# Assign.net
KiCad netlist of a schematic drawn in Altium Designer
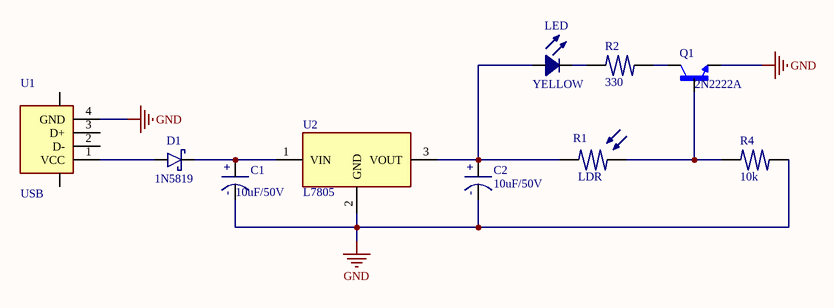
[diagram p0: Assign.SchDoc]

(export (version "E")
  (design (tool "Eeschema 10.0.6"))
  (components
    (comp (ref "C1")
      (value "10uF/50V")
      (footprint "10uF/50V")
      (description "Electrolytic Capacitor 10uF/50V")
      (libsource (lib "Electrolytic Capacitor") (part "10uF/50V"))
    )
    (comp (ref "C2")
      (value "10uF/50V")
      (footprint "10uF/50V")
      (description "Electrolytic Capacitor 10uF/50V")
      (libsource (lib "Electrolytic Capacitor") (part "10uF/50V"))
    )
    (comp (ref "D1")
      (value "1N5819")
      (footprint "1N5819")
      (description "Rectifier Schottky 40V 1A DO-15")
      (libsource (lib "Diode") (part "1N5819"))
    )
    (comp (ref "LED")
      (value "YELLOW")
      (footprint "LED_0805_YELLOW")
      (description "LED 0805 Yellow.")
      (libsource (lib "LED") (part "LED_0805_YELLOW"))
    )
    (comp (ref "Q1")
      (value "2N2222A")
      (footprint "TO92254P470H750-3")
      (description "Bipolar (BJT) Transistor NPN 40 V 600 mA 250MHz 625 mW Through Hole TO-92")
      (fields (field (name "MF") "Diotec Semiconductor"))
      (libsource (lib "2N2222A") (part "2N2222A"))
    )
    (comp (ref "R1")
      (value "LDR")
      (footprint "LDR")
      (description "LIGHT DEPENDEND RESISTOR/PHOTORESITOR")
      (libsource (lib "Sensors") (part "LDR"))
    )
    (comp (ref "R2")
      (value "330")
      (footprint "RESISTOR_PTH_9.5mm")
      (description "Generic Resistor 9.5mm.")
      (libsource (lib "Resistors") (part "RESISTOR_9.5mm"))
    )
    (comp (ref "R4")
      (value "10k")
      (footprint "RESISTOR_PTH_9.5mm")
      (description "Generic Resistor 9.5mm.")
      (libsource (lib "Resistors") (part "RESISTOR_9.5mm"))
    )
    (comp (ref "U1") (value "USB") (footprint "USB") (libsource (lib "Connectors") (part "USB")))
    (comp (ref "U2")
      (value "L7805")
      (footprint "L7805_smd")
      (description "IC REG LINEAR 5V 1.5A TO220AB")
      (libsource (lib "Voltage Regulators") (part "L7805"))
    )
  )
  (nets
    (net (code "1") (name "GND") (class "Default")
      (node (ref "C1") (pin "1") (pinfunction "1_1") (pintype "passive"))
      (node (ref "C2") (pin "1") (pinfunction "1_1") (pintype "passive"))
      (node (ref "Q1") (pin "1") (pinfunction "E_1") (pintype "passive"))
      (node (ref "R4") (pin "2") (pinfunction "2_2") (pintype "passive"))
      (node (ref "U1") (pin "4") (pinfunction "GND_4") (pintype "passive"))
      (node (ref "U2") (pin "2") (pinfunction "GND_2") (pintype "passive"))
    )
    (net (code "2") (name "Net-(C1-_2)") (class "Default")
      (node (ref "C1") (pin "2") (pinfunction "_2_2") (pintype "passive"))
      (node (ref "D1") (pin "2") (pintype "passive"))
      (node (ref "U2") (pin "1") (pinfunction "VIN_1") (pintype "passive"))
    )
    (net (code "3") (name "Net-(C2-_2)") (class "Default")
      (node (ref "C2") (pin "2") (pinfunction "_2_2") (pintype "passive"))
      (node (ref "LED") (pin "1") (pinfunction "1_1") (pintype "passive"))
      (node (ref "R1") (pin "1") (pinfunction "1_1") (pintype "passive"))
      (node (ref "U2") (pin "3") (pinfunction "VOUT_3") (pintype "passive"))
    )
    (net (code "4") (name "Net-(LED-Pad2)") (class "Default")
      (node (ref "LED") (pin "2") (pinfunction "2_2") (pintype "passive"))
      (node (ref "R2") (pin "1") (pinfunction "1_1") (pintype "passive"))
    )
    (net (code "5") (name "Net-(Q1-B)") (class "Default")
      (node (ref "Q1") (pin "2") (pinfunction "B_2") (pintype "passive"))
      (node (ref "R1") (pin "2") (pinfunction "2_2") (pintype "passive"))
      (node (ref "R4") (pin "1") (pinfunction "1_1") (pintype "passive"))
    )
    (net (code "6") (name "Net-(Q1-C)") (class "Default")
      (node (ref "Q1") (pin "3") (pinfunction "C_3") (pintype "passive"))
      (node (ref "R2") (pin "2") (pinfunction "2_2") (pintype "passive"))
    )
    (net (code "7") (name "Net-(U1-VCC)") (class "Default")
      (node (ref "D1") (pin "1") (pinfunction "1_1") (pintype "passive"))
      (node (ref "U1") (pin "1") (pinfunction "VCC_1") (pintype "passive"))
    )
    (net (code "8") (name "unconnected-(U1-D+-Pad3)") (class "Default")
      (node (ref "U1") (pin "3") (pinfunction "D+_3") (pintype "passive"))
    )
    (net (code "9") (name "unconnected-(U1-D--Pad2)") (class "Default")
      (node (ref "U1") (pin "2") (pinfunction "D-_2") (pintype "passive"))
    )
  )
)
